# RSeries_VCSensor_v1_1.net
KiCad netlist of a schematic drawn in EAGLE
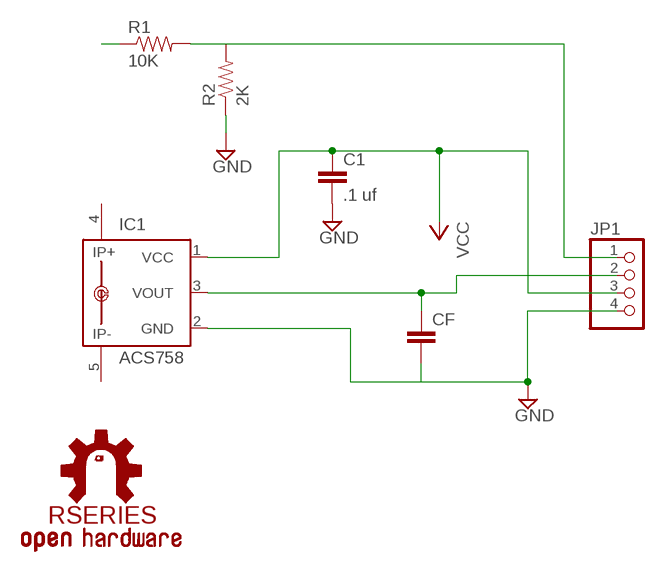
[diagram p0: schematic, sheet 1]

(export (version "E")
  (design (tool "Eeschema 10.0.6"))
  (components
    (comp (ref "C1")
      (value ".1 uf")
      (footprint "eagle-import:CAP-PTH-SMALL")
      (libsource (lib "eagle-import") (part "CAPPTH"))
    )
    (comp (ref "CF")
      (value "CAPPTH1")
      (footprint "eagle-import:CAP-PTH-5MM")
      (libsource (lib "eagle-import") (part "CAPPTH1"))
    )
    (comp (ref "IC1")
      (value "ACS758")
      (footprint "eagle-import:CB-PFF")
      (fields (field (name "MPN") "ACS758LCB-050B-PFF-T"))
      (libsource (lib "eagle-import") (part "ACS758LCB-050B-PFF-T"))
    )
    (comp (ref "JP1")
      (value "PINHD-1X4")
      (footprint "eagle-import:1X04")
      (libsource (lib "eagle-import") (part "PINHD-1X4"))
    )
    (comp (ref "R1")
      (value "10K")
      (footprint "eagle-import:AXIAL-0.4")
      (libsource (lib "eagle-import") (part "RESISTORPTH-1/4W"))
    )
    (comp (ref "R2")
      (value "2K")
      (footprint "eagle-import:AXIAL-0.4")
      (libsource (lib "eagle-import") (part "RESISTORPTH-1/4W"))
    )
    (comp (ref "U$1")
      (value "RSERIES-OSHW-LOGO")
      (footprint "eagle-import:RSERIES-OSHW-LOGO-LARGE")
      (libsource (lib "eagle-import") (part "RSERIES-OSHW-LOGO"))
    )
  )
  (nets
    (net (code "1") (name "GND") (class "Default")
      (node (ref "C1") (pin "2") (pinfunction "2_2") (pintype "passive"))
      (node (ref "CF") (pin "2") (pinfunction "2_2") (pintype "passive"))
      (node (ref "IC1") (pin "2") (pinfunction "GND_2") (pintype "power_in"))
      (node (ref "JP1") (pin "4") (pinfunction "4_4") (pintype "passive"))
      (node (ref "R2") (pin "P$1") (pinfunction "1_P$1") (pintype "passive"))
    )
    (net (code "2") (name "Net-(IC1-VOUT)") (class "Default")
      (node (ref "CF") (pin "1") (pinfunction "1_1") (pintype "passive"))
      (node (ref "IC1") (pin "3") (pinfunction "VOUT_3") (pintype "output"))
      (node (ref "JP1") (pin "2") (pinfunction "2_2") (pintype "passive"))
    )
    (net (code "3") (name "Net-(R1-2)") (class "Default")
      (node (ref "JP1") (pin "1") (pinfunction "1_1") (pintype "passive"))
      (node (ref "R1") (pin "P$2") (pinfunction "2_P$2") (pintype "passive"))
      (node (ref "R2") (pin "P$2") (pinfunction "2_P$2") (pintype "passive"))
    )
    (net (code "4") (name "VCC") (class "Default")
      (node (ref "C1") (pin "1") (pinfunction "1_1") (pintype "passive"))
      (node (ref "IC1") (pin "1") (pinfunction "VCC_1") (pintype "power_in"))
      (node (ref "JP1") (pin "3") (pinfunction "3_3") (pintype "passive"))
    )
    (net (code "5") (name "unconnected-(IC1-IP+-Pad4)") (class "Default")
      (node (ref "IC1") (pin "4") (pinfunction "IP+_4") (pintype "passive"))
    )
    (net (code "6") (name "unconnected-(IC1-IP--Pad5)") (class "Default")
      (node (ref "IC1") (pin "5") (pinfunction "IP-_5") (pintype "passive"))
    )
    (net (code "7") (name "unconnected-(IC1-PadIP+1)") (class "Default")
      (node (ref "IC1") (pin "IP+1") (pinfunction "IP+1_IP+1") (pintype "input"))
    )
    (net (code "8") (name "unconnected-(IC1-PadIP-1)") (class "Default")
      (node (ref "IC1") (pin "IP-1") (pinfunction "IP-1_IP-1") (pintype "input"))
    )
    (net (code "9") (name "unconnected-(R1-1-PadP$1)") (class "Default")
      (node (ref "R1") (pin "P$1") (pinfunction "1_P$1") (pintype "passive"))
    )
  )
)
